# Luftschiff_V0_1.net
KiCad netlist of a schematic drawn in EAGLE
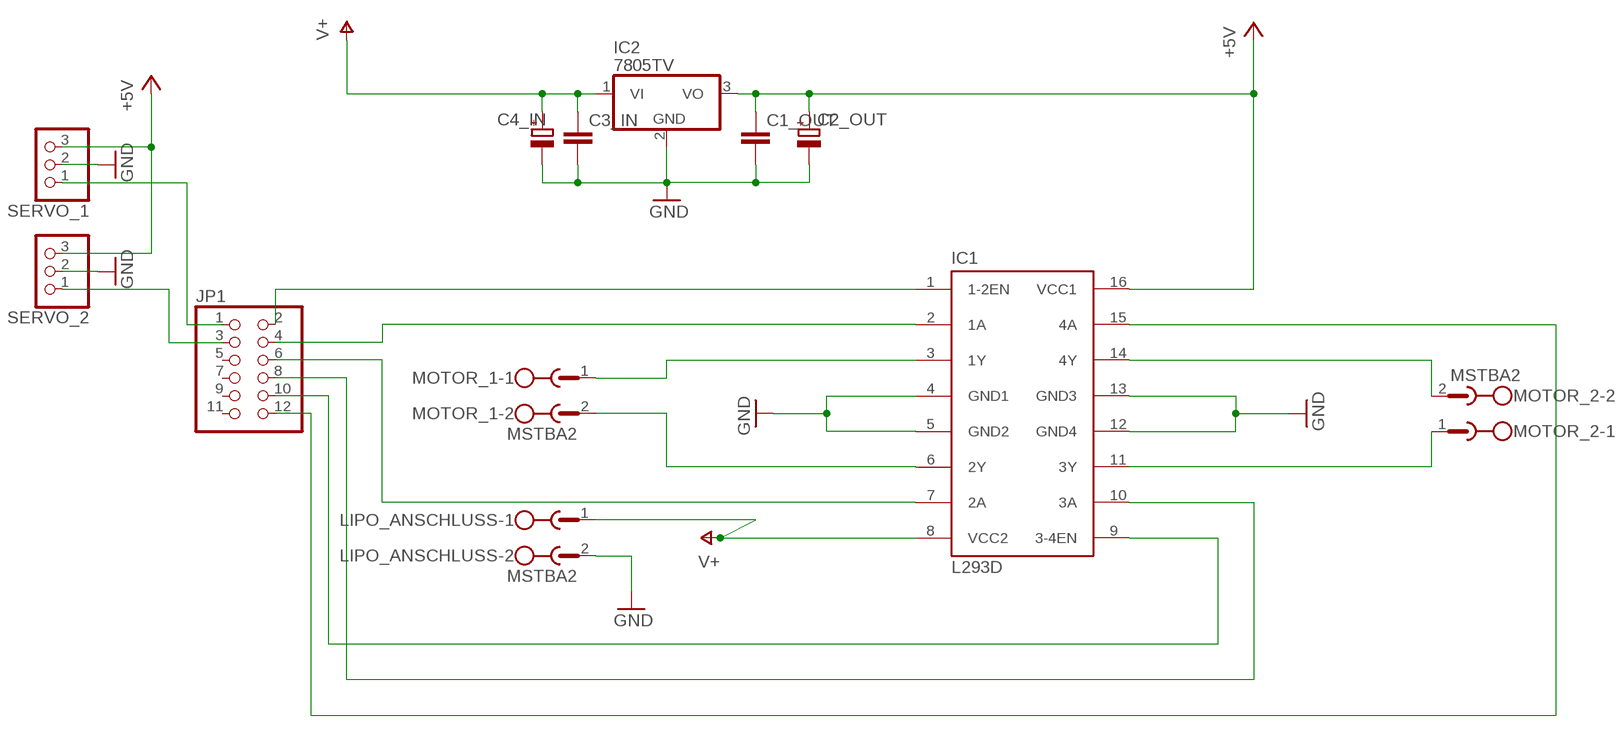
[diagram p0: schematic, sheet 1]

(export (version "E")
  (design (tool "Eeschema 10.0.6"))
  (components
    (comp (ref "C1_OUT")
      (value "C-EU025-040X050")
      (footprint "eagle-import:C025-040X050")
      (libsource (lib "eagle-import") (part "C-EU025-040X050"))
    )
    (comp (ref "C2_OUT")
      (value "CPOL-EUE2.5-6")
      (footprint "eagle-import:E2,5-6")
      (libsource (lib "eagle-import") (part "CPOL-EUE2.5-6"))
    )
    (comp (ref "C3_IN")
      (value "C-EU025-040X050")
      (footprint "eagle-import:C025-040X050")
      (libsource (lib "eagle-import") (part "C-EU025-040X050"))
    )
    (comp (ref "C4_IN")
      (value "CPOL-EUE2.5-6")
      (footprint "eagle-import:E2,5-6")
      (libsource (lib "eagle-import") (part "CPOL-EUE2.5-6"))
    )
    (comp (ref "IC1")
      (value "L293D")
      (footprint "eagle-import:DIL16")
      (libsource (lib "eagle-import") (part "L293D"))
    )
    (comp (ref "IC2")
      (value "7805TV")
      (footprint "eagle-import:TO220V")
      (libsource (lib "eagle-import") (part "78TV05"))
    )
    (comp (ref "JP1")
      (value "PINHD-2X6/90")
      (footprint "eagle-import:2X06_90")
      (libsource (lib "eagle-import") (part "PINHD-2X6/90"))
    )
    (comp (ref "LIPO_ANSCHLUSS")
      (value "MSTBA2")
      (footprint "eagle-import:MSTBA2")
      (fields (field (name "MF") "FARNELL") (field (name "MPN") "1757242"))
      (libsource (lib "eagle-import") (part "MSTBA2"))
    )
    (comp (ref "MOTOR_1")
      (value "MSTBA2")
      (footprint "eagle-import:MSTBA2")
      (fields (field (name "MF") "FARNELL") (field (name "MPN") "1757242"))
      (libsource (lib "eagle-import") (part "MSTBA2"))
    )
    (comp (ref "MOTOR_2")
      (value "MSTBA2")
      (footprint "eagle-import:MSTBA2")
      (fields (field (name "MF") "FARNELL") (field (name "MPN") "1757242"))
      (libsource (lib "eagle-import") (part "MSTBA2"))
    )
    (comp (ref "SERVO_1")
      (value "PINHD-1X3")
      (footprint "eagle-import:1X03")
      (libsource (lib "eagle-import") (part "PINHD-1X3"))
    )
    (comp (ref "SERVO_2")
      (value "PINHD-1X3")
      (footprint "eagle-import:1X03")
      (libsource (lib "eagle-import") (part "PINHD-1X3"))
    )
  )
  (nets
    (net (code "1") (name "+5V") (class "Default")
      (node (ref "C1_OUT") (pin "1") (pinfunction "1_1") (pintype "passive"))
      (node (ref "C2_OUT") (pin "+") (pinfunction "+_+") (pintype "passive"))
      (node (ref "IC1") (pin "16") (pinfunction "VCC1_16") (pintype "power_in"))
      (node (ref "IC2") (pin "3") (pinfunction "VO_3") (pintype "passive"))
      (node (ref "SERVO_1") (pin "3") (pinfunction "3_3") (pintype "passive"))
      (node (ref "SERVO_2") (pin "3") (pinfunction "3_3") (pintype "passive"))
    )
    (net (code "2") (name "GND") (class "Default")
      (node (ref "C1_OUT") (pin "2") (pinfunction "2_2") (pintype "passive"))
      (node (ref "C2_OUT") (pin "-") (pinfunction "-_-") (pintype "passive"))
      (node (ref "C3_IN") (pin "2") (pinfunction "2_2") (pintype "passive"))
      (node (ref "C4_IN") (pin "-") (pinfunction "-_-") (pintype "passive"))
      (node (ref "IC1") (pin "12") (pinfunction "GND4_12") (pintype "power_in"))
      (node (ref "IC1") (pin "13") (pinfunction "GND3_13") (pintype "power_in"))
      (node (ref "IC1") (pin "4") (pinfunction "GND1_4") (pintype "power_in"))
      (node (ref "IC1") (pin "5") (pinfunction "GND2_5") (pintype "power_in"))
      (node (ref "IC2") (pin "2") (pinfunction "GND_2") (pintype "passive"))
      (node (ref "LIPO_ANSCHLUSS") (pin "2") (pinfunction "1_2") (pintype "passive"))
      (node (ref "SERVO_1") (pin "2") (pinfunction "2_2") (pintype "passive"))
      (node (ref "SERVO_2") (pin "2") (pinfunction "2_2") (pintype "passive"))
    )
    (net (code "3") (name "Net-(IC1-1-2EN)") (class "Default")
      (node (ref "IC1") (pin "1") (pinfunction "1-2EN_1") (pintype "input"))
      (node (ref "JP1") (pin "2") (pinfunction "2_2") (pintype "passive"))
    )
    (net (code "4") (name "Net-(IC1-1A)") (class "Default")
      (node (ref "IC1") (pin "2") (pinfunction "1A_2") (pintype "input"))
      (node (ref "JP1") (pin "4") (pinfunction "4_4") (pintype "passive"))
    )
    (net (code "5") (name "Net-(IC1-1Y)") (class "Default")
      (node (ref "IC1") (pin "3") (pinfunction "1Y_3") (pintype "output"))
      (node (ref "MOTOR_1") (pin "1") (pinfunction "1_1") (pintype "passive"))
    )
    (net (code "6") (name "Net-(IC1-2A)") (class "Default")
      (node (ref "IC1") (pin "7") (pinfunction "2A_7") (pintype "input"))
      (node (ref "JP1") (pin "6") (pinfunction "6_6") (pintype "passive"))
    )
    (net (code "7") (name "Net-(IC1-2Y)") (class "Default")
      (node (ref "IC1") (pin "6") (pinfunction "2Y_6") (pintype "output"))
      (node (ref "MOTOR_1") (pin "2") (pinfunction "1_2") (pintype "passive"))
    )
    (net (code "8") (name "Net-(IC1-3-4EN)") (class "Default")
      (node (ref "IC1") (pin "9") (pinfunction "3-4EN_9") (pintype "input"))
      (node (ref "JP1") (pin "10") (pinfunction "10_10") (pintype "passive"))
    )
    (net (code "9") (name "Net-(IC1-3A)") (class "Default")
      (node (ref "IC1") (pin "10") (pinfunction "3A_10") (pintype "input"))
      (node (ref "JP1") (pin "8") (pinfunction "8_8") (pintype "passive"))
    )
    (net (code "10") (name "Net-(IC1-3Y)") (class "Default")
      (node (ref "IC1") (pin "11") (pinfunction "3Y_11") (pintype "output"))
      (node (ref "MOTOR_2") (pin "1") (pinfunction "1_1") (pintype "passive"))
    )
    (net (code "11") (name "Net-(IC1-4A)") (class "Default")
      (node (ref "IC1") (pin "15") (pinfunction "4A_15") (pintype "input"))
      (node (ref "JP1") (pin "12") (pinfunction "12_12") (pintype "passive"))
    )
    (net (code "12") (name "Net-(IC1-4Y)") (class "Default")
      (node (ref "IC1") (pin "14") (pinfunction "4Y_14") (pintype "output"))
      (node (ref "MOTOR_2") (pin "2") (pinfunction "1_2") (pintype "passive"))
    )
    (net (code "13") (name "Net-(JP1-Pad1)") (class "Default")
      (node (ref "JP1") (pin "1") (pinfunction "1_1") (pintype "passive"))
      (node (ref "SERVO_1") (pin "1") (pinfunction "1_1") (pintype "passive"))
    )
    (net (code "14") (name "Net-(JP1-Pad3)") (class "Default")
      (node (ref "JP1") (pin "3") (pinfunction "3_3") (pintype "passive"))
      (node (ref "SERVO_2") (pin "1") (pinfunction "1_1") (pintype "passive"))
    )
    (net (code "15") (name "V+") (class "Default")
      (node (ref "C3_IN") (pin "1") (pinfunction "1_1") (pintype "passive"))
      (node (ref "C4_IN") (pin "+") (pinfunction "+_+") (pintype "passive"))
      (node (ref "IC1") (pin "8") (pinfunction "VCC2_8") (pintype "power_in"))
      (node (ref "IC2") (pin "1") (pinfunction "VI_1") (pintype "input"))
      (node (ref "LIPO_ANSCHLUSS") (pin "1") (pinfunction "1_1") (pintype "passive"))
    )
    (net (code "16") (name "unconnected-(JP1-Pad5)") (class "Default")
      (node (ref "JP1") (pin "5") (pinfunction "5_5") (pintype "passive"))
    )
    (net (code "17") (name "unconnected-(JP1-Pad7)") (class "Default")
      (node (ref "JP1") (pin "7") (pinfunction "7_7") (pintype "passive"))
    )
    (net (code "18") (name "unconnected-(JP1-Pad9)") (class "Default")
      (node (ref "JP1") (pin "9") (pinfunction "9_9") (pintype "passive"))
    )
    (net (code "19") (name "unconnected-(JP1-Pad11)") (class "Default")
      (node (ref "JP1") (pin "11") (pinfunction "11_11") (pintype "passive"))
    )
  )
)
